# 16_DEBUG.net
KiCad netlist of a schematic drawn in Altium Designer
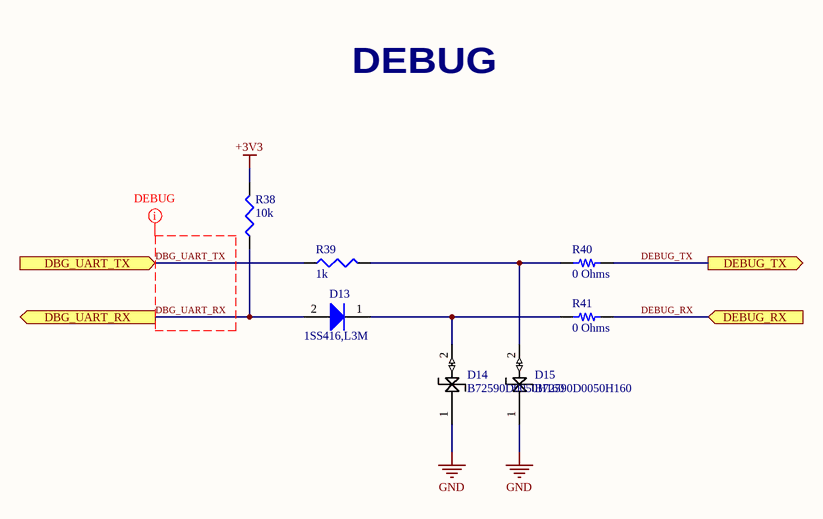
[diagram p0: 16_DEBUG.SchDoc]

(export (version "E")
  (design (tool "Eeschema 10.0.6"))
  (components
    (comp (ref "D13")
      (value "1SS416,L3M")
      (footprint "SOD-923-2")
      (description "Diode 30 V 100mA Surface Mount SOD-923")
      (fields
        (field (name "LCSC MANUFACTURER PART NUMBER") "1SS416,L3M(B")
        (field (name "LCSC PART NUMBER") "C2943683")
        (field (name "MANUFACTURER PART NUMBER") "1SS416,L3M")
      )
      (libsource (lib "HW_HOLLAND_NCDM_MONITOR_R1") (part "1SS416,L3M"))
    )
    (comp (ref "D14")
      (value "B72590D0050H160")
      (footprint "SOD1005X60N")
      (description "VARISTOR 150V 0402")
      (fields (field (name "MANUFACTURER") "TDK EPCOS"))
      (libsource (lib "HW_HOLLAND_NCDM_MONITOR_R1") (part "B72590D0050H160"))
    )
    (comp (ref "D15")
      (value "B72590D0050H160")
      (footprint "SOD1005X60N")
      (description "VARISTOR 150V 0402")
      (fields (field (name "MANUFACTURER") "TDK EPCOS"))
      (libsource (lib "HW_HOLLAND_NCDM_MONITOR_R1") (part "B72590D0050H160"))
    )
    (comp (ref "R38")
      (value "10k")
      (footprint "RES0402(1005)")
      (description "10 kOhms ±1% 0.063W, 1/16W Chip Resistor 0402 (1005 Metric) Moisture Resistant Thick Film")
      (fields
        (field (name "MANUFACTURER PART NUMBER") "RC0402FR-0710KL")
        (field (name "LCSC PART NUMBER") "C60490")
      )
      (libsource (lib "HW_HOLLAND_NCDM_MONITOR_R1") (part "RES0402_10K_%1"))
    )
    (comp (ref "R39")
      (value "1k")
      (footprint "RES0402(1005)")
      (description "1 kOhms ±1% 0.063W, 1/16W Chip Resistor 0402 (1005 Metric) Moisture Resistant Thick Film")
      (fields
        (field (name "MANUFACTURER PART NUMBER") "RC0402FR-071KL")
        (field (name "LCSC PART NUMBER") "C106235")
      )
      (libsource (lib "HW_HOLLAND_NCDM_MONITOR_R1") (part "RES0402_1K_%1"))
    )
    (comp (ref "R40")
      (value "0 Ohms")
      (footprint "RES 0402_1005")
      (description "RES 0 OHM JUMPER 1/8W 0402")
      (fields
        (field (name "PART NUMBER") "HCJ0402ZT0R00")
        (field (name "MANUFACTURER") "Stackpole Electronics Inc")
      )
      (libsource (lib "Celestial Altium Library - altium_library") (part "Resistor"))
    )
    (comp (ref "R41")
      (value "0 Ohms")
      (footprint "RES 0402_1005")
      (description "RES 0 OHM JUMPER 1/8W 0402")
      (fields
        (field (name "PART NUMBER") "HCJ0402ZT0R00")
        (field (name "MANUFACTURER") "Stackpole Electronics Inc")
      )
      (libsource (lib "Celestial Altium Library - altium_library") (part "Resistor"))
    )
  )
  (nets
    (net (code "1") (name "+3V3") (class "Default")
      (node (ref "R38") (pin "2") (pinfunction "2_2") (pintype "passive"))
    )
    (net (code "2") (name "/DBG_UART_RX") (class "Default")
      (node (ref "D13") (pin "2") (pinfunction "A_2") (pintype "passive"))
      (node (ref "R38") (pin "1") (pinfunction "1_1") (pintype "passive"))
    )
    (net (code "3") (name "/DBG_UART_TX") (class "Default")
      (node (ref "R39") (pin "2") (pinfunction "2_2") (pintype "passive"))
    )
    (net (code "4") (name "/DEBUG_RX") (class "Default")
      (node (ref "R41") (pin "1") (pinfunction "1_1") (pintype "passive"))
    )
    (net (code "5") (name "/DEBUG_TX") (class "Default")
      (node (ref "R40") (pin "1") (pinfunction "1_1") (pintype "passive"))
    )
    (net (code "6") (name "GND") (class "Default")
      (node (ref "D14") (pin "1") (pinfunction "GND_1") (pintype "passive"))
      (node (ref "D15") (pin "1") (pinfunction "GND_1") (pintype "passive"))
    )
    (net (code "7") (name "Net-(D13-K)") (class "Default")
      (node (ref "D13") (pin "1") (pinfunction "K_1") (pintype "passive"))
      (node (ref "D14") (pin "2") (pinfunction "I/OLINE_2") (pintype "bidirectional"))
      (node (ref "R41") (pin "2") (pinfunction "2_2") (pintype "passive"))
    )
    (net (code "8") (name "Net-(D15-I{slash}OLINE)") (class "Default")
      (node (ref "D15") (pin "2") (pinfunction "I/OLINE_2") (pintype "bidirectional"))
      (node (ref "R39") (pin "1") (pinfunction "1_1") (pintype "passive"))
      (node (ref "R40") (pin "2") (pinfunction "2_2") (pintype "passive"))
    )
  )
)
